# nRF24_Raspberry_Pi_adapter.net
KiCad netlist of a schematic drawn in EAGLE
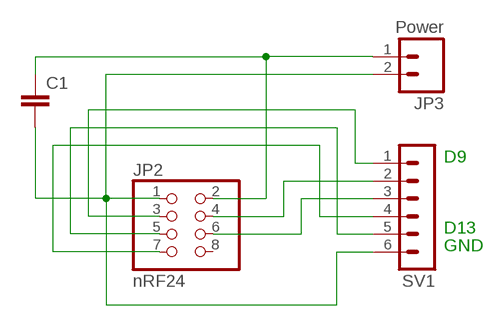
[diagram p0: schematic, sheet 1]

(export (version "E")
  (design (tool "Eeschema 10.0.6"))
  (components
    (comp (ref "C1")
      (value "C2,5-3")
      (footprint "eagle-import:C2.5-3")
      (libsource (lib "eagle-import") (part "C2,5-3"))
    )
    (comp (ref "JP2")
      (value "nRF24")
      (footprint "eagle-import:2X04")
      (libsource (lib "eagle-import") (part "PINHD-2X4"))
    )
    (comp (ref "JP3")
      (value "Power")
      (footprint "eagle-import:1X02_LOCK_LONGPADS")
      (libsource (lib "eagle-import") (part "M02LOCK_LONGPADS"))
    )
    (comp (ref "SV1")
      (value "MA06-1")
      (footprint "eagle-import:MA06-1")
      (libsource (lib "eagle-import") (part "MA06-1"))
    )
  )
  (nets
    (net (code "1") (name "Net-(C1-Pad1)") (class "Default")
      (node (ref "C1") (pin "1") (pinfunction "1_1") (pintype "passive"))
      (node (ref "JP2") (pin "2") (pinfunction "2_2") (pintype "passive"))
      (node (ref "JP3") (pin "1") (pinfunction "1_1") (pintype "passive"))
    )
    (net (code "2") (name "Net-(C1-Pad2)") (class "Default")
      (node (ref "C1") (pin "2") (pinfunction "2_2") (pintype "passive"))
      (node (ref "JP2") (pin "1") (pinfunction "1_1") (pintype "passive"))
      (node (ref "JP3") (pin "2") (pinfunction "2_2") (pintype "passive"))
      (node (ref "SV1") (pin "6") (pinfunction "6_6") (pintype "passive"))
    )
    (net (code "3") (name "Net-(JP2-Pad3)") (class "Default")
      (node (ref "JP2") (pin "3") (pinfunction "3_3") (pintype "passive"))
      (node (ref "SV1") (pin "1") (pinfunction "1_1") (pintype "passive"))
    )
    (net (code "4") (name "Net-(JP2-Pad4)") (class "Default")
      (node (ref "JP2") (pin "4") (pinfunction "4_4") (pintype "passive"))
      (node (ref "SV1") (pin "2") (pinfunction "2_2") (pintype "passive"))
    )
    (net (code "5") (name "Net-(JP2-Pad5)") (class "Default")
      (node (ref "JP2") (pin "5") (pinfunction "5_5") (pintype "passive"))
      (node (ref "SV1") (pin "5") (pinfunction "5_5") (pintype "passive"))
    )
    (net (code "6") (name "Net-(JP2-Pad6)") (class "Default")
      (node (ref "JP2") (pin "6") (pinfunction "6_6") (pintype "passive"))
      (node (ref "SV1") (pin "3") (pinfunction "3_3") (pintype "passive"))
    )
    (net (code "7") (name "Net-(JP2-Pad7)") (class "Default")
      (node (ref "JP2") (pin "7") (pinfunction "7_7") (pintype "passive"))
      (node (ref "SV1") (pin "4") (pinfunction "4_4") (pintype "passive"))
    )
    (net (code "8") (name "unconnected-(JP2-Pad8)") (class "Default")
      (node (ref "JP2") (pin "8") (pinfunction "8_8") (pintype "passive"))
    )
  )
)
